# Urukul_FPGA_Supply.net
KiCad netlist of a schematic drawn in Altium Designer
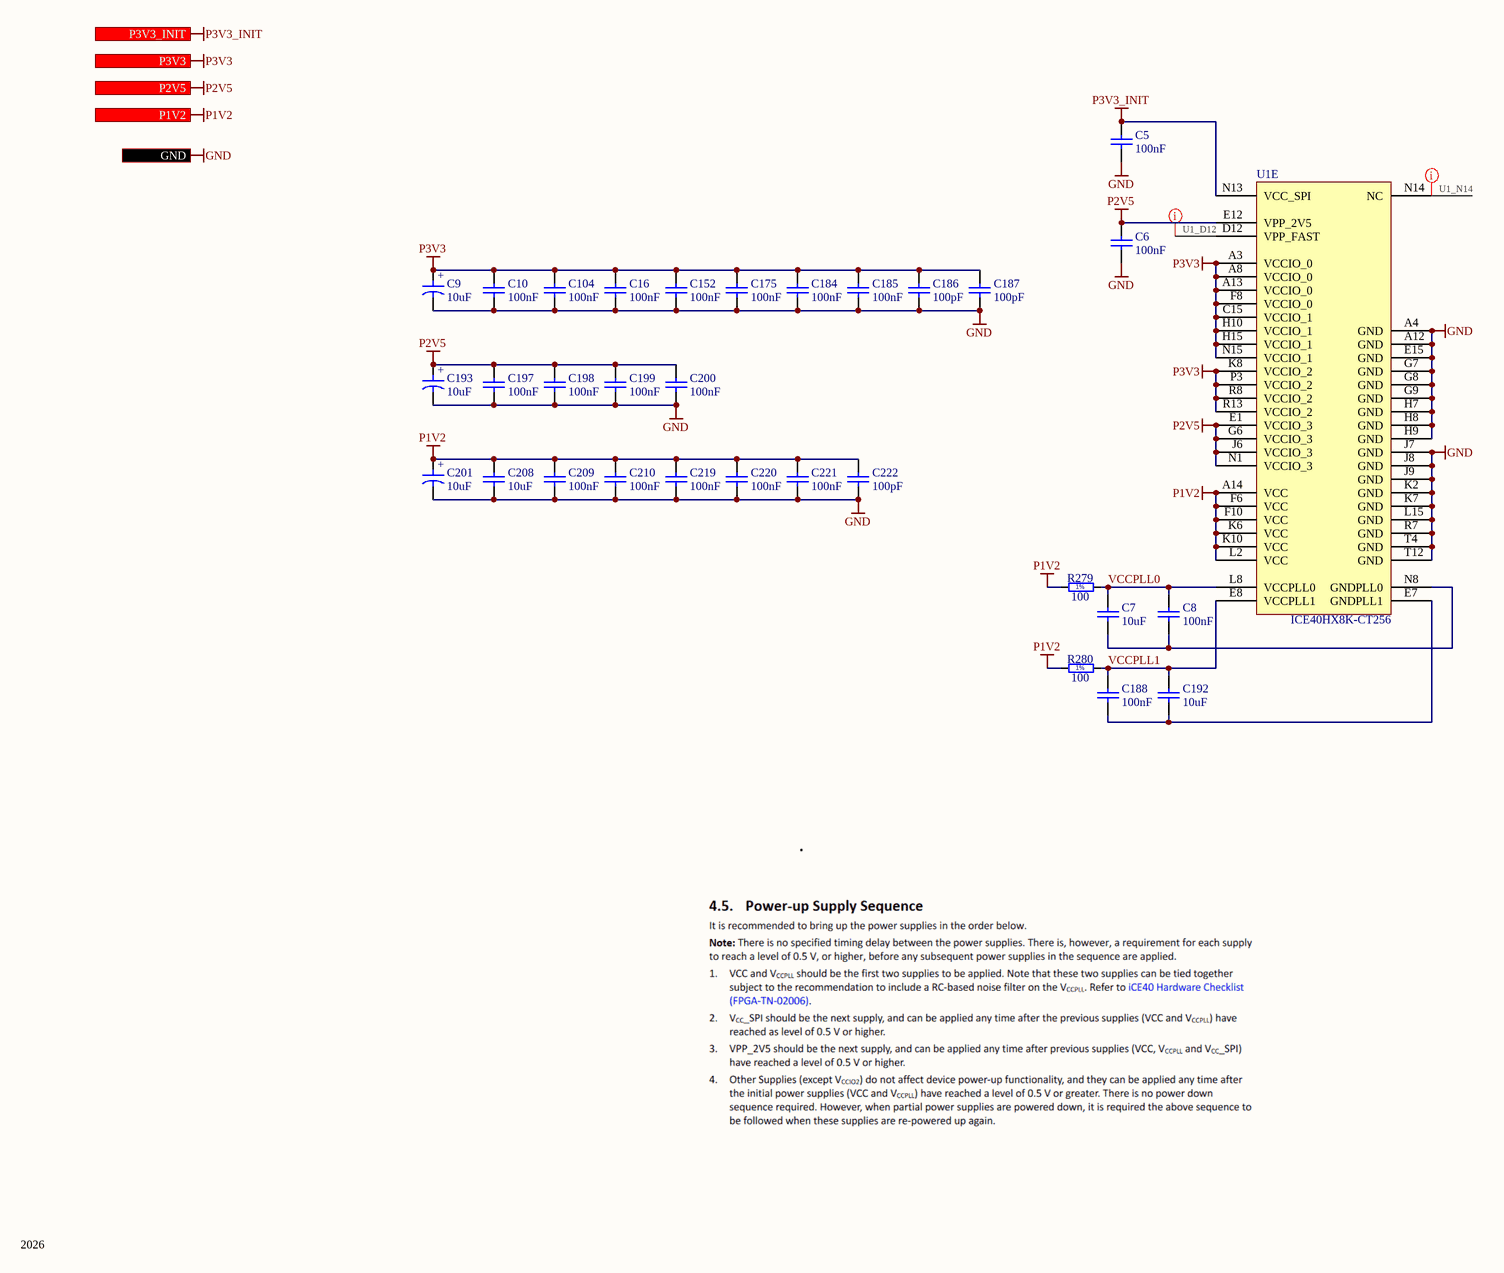
[diagram p0: Urukul_FPGA_Supply.SchDoc]

(export (version "E")
  (design (tool "Eeschema 10.0.6"))
  (components
    (comp (ref "C5")
      (value "100nF")
      (footprint "CAPC1005X55N")
      (description "Non-polarised capacitor")
      (fields
        (field (name "PART NUMBER") "CC0402_100NF_16V_10%_X5R")
        (field (name "VOLTAGE") "16V")
        (field (name "AUTHOR") "CERN DEM JLC")
      )
      (libsource (lib "Capacitors") (part "Capacitor - non polarized"))
    )
    (comp (ref "C6")
      (value "100nF")
      (footprint "CAPC1005X55N")
      (description "Non-polarised capacitor")
      (fields
        (field (name "PART NUMBER") "CC0402_100NF_16V_10%_X5R")
        (field (name "VOLTAGE") "16V")
        (field (name "AUTHOR") "CERN DEM JLC")
      )
      (libsource (lib "Capacitors") (part "Capacitor - non polarized"))
    )
    (comp (ref "C7")
      (value "10uF")
      (footprint "CAPC1005X70N")
      (description "Non-polarised capacitor")
      (fields
        (field (name "PART NUMBER") "CC0402_10UF_6.3V_20%_X5R")
        (field (name "VOLTAGE") "6.3V")
        (field (name "AUTHOR") "CERN DEM JLC")
      )
      (libsource (lib "Capacitors") (part "Capacitor - non polarized"))
    )
    (comp (ref "C8")
      (value "100nF")
      (footprint "CAPC1005X55N")
      (description "Non-polarised capacitor")
      (fields
        (field (name "PART NUMBER") "CC0402_100NF_16V_10%_X5R")
        (field (name "VOLTAGE") "16V")
        (field (name "AUTHOR") "CERN DEM JLC")
      )
      (libsource (lib "Capacitors") (part "Capacitor - non polarized"))
    )
    (comp (ref "C9")
      (value "10uF")
      (footprint "CAPMP3216X180N")
      (description "Polarised capacitor")
      (fields
        (field (name "PART NUMBER") "CTE3216-18_10UF_16V_20%_AVX_TCJ")
        (field (name "VOLTAGE") "16V")
        (field (name "AUTHOR") "CERN DEM JLC")
      )
      (libsource (lib "Capacitors") (part "Capacitor - polarized"))
    )
    (comp (ref "C10")
      (value "100nF")
      (footprint "CAPC1005X55N")
      (description "Non-polarised capacitor")
      (fields
        (field (name "PART NUMBER") "CC0402_100NF_16V_10%_X5R")
        (field (name "VOLTAGE") "16V")
        (field (name "AUTHOR") "CERN DEM JLC")
      )
      (libsource (lib "Capacitors") (part "Capacitor - non polarized"))
    )
    (comp (ref "C16")
      (value "100nF")
      (footprint "CAPC1005X55N")
      (description "Non-polarised capacitor")
      (fields
        (field (name "PART NUMBER") "CC0402_100NF_16V_10%_X5R")
        (field (name "VOLTAGE") "16V")
        (field (name "AUTHOR") "CERN DEM JLC")
      )
      (libsource (lib "Capacitors") (part "Capacitor - non polarized"))
    )
    (comp (ref "C104")
      (value "100nF")
      (footprint "CAPC1005X55N")
      (description "Non-polarised capacitor")
      (fields
        (field (name "PART NUMBER") "CC0402_100NF_16V_10%_X5R")
        (field (name "VOLTAGE") "16V")
        (field (name "AUTHOR") "CERN DEM JLC")
      )
      (libsource (lib "Capacitors") (part "Capacitor - non polarized"))
    )
    (comp (ref "C152")
      (value "100nF")
      (footprint "CAPC1005X55N")
      (description "Non-polarised capacitor")
      (fields
        (field (name "PART NUMBER") "CC0402_100NF_16V_10%_X5R")
        (field (name "VOLTAGE") "16V")
        (field (name "AUTHOR") "CERN DEM JLC")
      )
      (libsource (lib "Capacitors") (part "Capacitor - non polarized"))
    )
    (comp (ref "C175")
      (value "100nF")
      (footprint "CAPC1005X55N")
      (description "Non-polarised capacitor")
      (fields
        (field (name "PART NUMBER") "CC0402_100NF_16V_10%_X5R")
        (field (name "VOLTAGE") "16V")
        (field (name "AUTHOR") "CERN DEM JLC")
      )
      (libsource (lib "Capacitors") (part "Capacitor - non polarized"))
    )
    (comp (ref "C184")
      (value "100nF")
      (footprint "CAPC1005X55N")
      (description "Non-polarised capacitor")
      (fields
        (field (name "PART NUMBER") "CC0402_100NF_16V_10%_X5R")
        (field (name "VOLTAGE") "16V")
        (field (name "AUTHOR") "CERN DEM JLC")
      )
      (libsource (lib "Capacitors") (part "Capacitor - non polarized"))
    )
    (comp (ref "C185")
      (value "100nF")
      (footprint "CAPC1005X55N")
      (description "Non-polarised capacitor")
      (fields
        (field (name "PART NUMBER") "CC0402_100NF_16V_10%_X5R")
        (field (name "VOLTAGE") "16V")
        (field (name "AUTHOR") "CERN DEM JLC")
      )
      (libsource (lib "Capacitors") (part "Capacitor - non polarized"))
    )
    (comp (ref "C186")
      (value "100pF")
      (footprint "CAPC1005X55N")
      (description "Non-polarised capacitor")
      (fields
        (field (name "PART NUMBER") "CC0402_100PF_50V_5%_C0G")
        (field (name "VOLTAGE") "50V")
        (field (name "AUTHOR") "CERN DEM JLC")
      )
      (libsource (lib "Capacitors") (part "Capacitor - non polarized"))
    )
    (comp (ref "C187")
      (value "100pF")
      (footprint "CAPC1005X55N")
      (description "Non-polarised capacitor")
      (fields
        (field (name "PART NUMBER") "CC0402_100PF_50V_5%_C0G")
        (field (name "VOLTAGE") "50V")
        (field (name "AUTHOR") "CERN DEM JLC")
      )
      (libsource (lib "Capacitors") (part "Capacitor - non polarized"))
    )
    (comp (ref "C188")
      (value "100nF")
      (footprint "CAPC1005X55N")
      (description "Non-polarised capacitor")
      (fields
        (field (name "PART NUMBER") "CC0402_100NF_16V_10%_X5R")
        (field (name "VOLTAGE") "16V")
        (field (name "AUTHOR") "CERN DEM JLC")
      )
      (libsource (lib "Capacitors") (part "Capacitor - non polarized"))
    )
    (comp (ref "C192")
      (value "10uF")
      (footprint "CAPC1005X70N")
      (description "Non-polarised capacitor")
      (fields
        (field (name "PART NUMBER") "CC0402_10UF_6.3V_20%_X5R")
        (field (name "VOLTAGE") "6.3V")
        (field (name "AUTHOR") "CERN DEM JLC")
      )
      (libsource (lib "Capacitors") (part "Capacitor - non polarized"))
    )
    (comp (ref "C193")
      (value "10uF")
      (footprint "CAPMP3216X180N")
      (description "Polarised capacitor")
      (fields
        (field (name "PART NUMBER") "CTE3216-18_10UF_16V_20%_AVX_TCJ")
        (field (name "VOLTAGE") "16V")
        (field (name "AUTHOR") "CERN DEM JLC")
      )
      (libsource (lib "Capacitors") (part "Capacitor - polarized"))
    )
    (comp (ref "C197")
      (value "100nF")
      (footprint "CAPC1005X55N")
      (description "Non-polarised capacitor")
      (fields
        (field (name "PART NUMBER") "CC0402_100NF_16V_10%_X5R")
        (field (name "VOLTAGE") "16V")
        (field (name "AUTHOR") "CERN DEM JLC")
      )
      (libsource (lib "Capacitors") (part "Capacitor - non polarized"))
    )
    (comp (ref "C198")
      (value "100nF")
      (footprint "CAPC1005X55N")
      (description "Non-polarised capacitor")
      (fields
        (field (name "PART NUMBER") "CC0402_100NF_16V_10%_X5R")
        (field (name "VOLTAGE") "16V")
        (field (name "AUTHOR") "CERN DEM JLC")
      )
      (libsource (lib "Capacitors") (part "Capacitor - non polarized"))
    )
    (comp (ref "C199")
      (value "100nF")
      (footprint "CAPC1005X55N")
      (description "Non-polarised capacitor")
      (fields
        (field (name "PART NUMBER") "CC0402_100NF_16V_10%_X5R")
        (field (name "VOLTAGE") "16V")
        (field (name "AUTHOR") "CERN DEM JLC")
      )
      (libsource (lib "Capacitors") (part "Capacitor - non polarized"))
    )
    (comp (ref "C200")
      (value "100nF")
      (footprint "CAPC1005X55N")
      (description "Non-polarised capacitor")
      (fields
        (field (name "PART NUMBER") "CC0402_100NF_16V_10%_X5R")
        (field (name "VOLTAGE") "16V")
        (field (name "AUTHOR") "CERN DEM JLC")
      )
      (libsource (lib "Capacitors") (part "Capacitor - non polarized"))
    )
    (comp (ref "C201")
      (value "10uF")
      (footprint "CAPMP3216X180N")
      (description "Polarised capacitor")
      (fields
        (field (name "PART NUMBER") "CTE3216-18_10UF_16V_20%_AVX_TCJ")
        (field (name "VOLTAGE") "16V")
        (field (name "AUTHOR") "CERN DEM JLC")
      )
      (libsource (lib "Capacitors") (part "Capacitor - polarized"))
    )
    (comp (ref "C208")
      (value "10uF")
      (footprint "CAPC2012X135N")
      (description "Non-polarised capacitor")
      (fields
        (field (name "PART NUMBER") "CC0805_10UF_16V_10%_X5R")
        (field (name "VOLTAGE") "16V")
        (field (name "AUTHOR") "CERN DEM JLC")
      )
      (libsource (lib "Capacitors") (part "Capacitor - non polarized"))
    )
    (comp (ref "C209")
      (value "100nF")
      (footprint "CAPC1005X55N")
      (description "Non-polarised capacitor")
      (fields
        (field (name "PART NUMBER") "CC0402_100NF_16V_10%_X5R")
        (field (name "VOLTAGE") "16V")
        (field (name "AUTHOR") "CERN DEM JLC")
      )
      (libsource (lib "Capacitors") (part "Capacitor - non polarized"))
    )
    (comp (ref "C210")
      (value "100nF")
      (footprint "CAPC1005X55N")
      (description "Non-polarised capacitor")
      (fields
        (field (name "PART NUMBER") "CC0402_100NF_16V_10%_X5R")
        (field (name "VOLTAGE") "16V")
        (field (name "AUTHOR") "CERN DEM JLC")
      )
      (libsource (lib "Capacitors") (part "Capacitor - non polarized"))
    )
    (comp (ref "C219")
      (value "100nF")
      (footprint "CAPC1005X55N")
      (description "Non-polarised capacitor")
      (fields
        (field (name "PART NUMBER") "CC0402_100NF_16V_10%_X5R")
        (field (name "VOLTAGE") "16V")
        (field (name "AUTHOR") "CERN DEM JLC")
      )
      (libsource (lib "Capacitors") (part "Capacitor - non polarized"))
    )
    (comp (ref "C220")
      (value "100nF")
      (footprint "CAPC1005X55N")
      (description "Non-polarised capacitor")
      (fields
        (field (name "PART NUMBER") "CC0402_100NF_16V_10%_X5R")
        (field (name "VOLTAGE") "16V")
        (field (name "AUTHOR") "CERN DEM JLC")
      )
      (libsource (lib "Capacitors") (part "Capacitor - non polarized"))
    )
    (comp (ref "C221")
      (value "100nF")
      (footprint "CAPC1005X55N")
      (description "Non-polarised capacitor")
      (fields
        (field (name "PART NUMBER") "CC0402_100NF_16V_10%_X5R")
        (field (name "VOLTAGE") "16V")
        (field (name "AUTHOR") "CERN DEM JLC")
      )
      (libsource (lib "Capacitors") (part "Capacitor - non polarized"))
    )
    (comp (ref "C222")
      (value "100pF")
      (footprint "CAPC1005X55N")
      (description "Non-polarised capacitor")
      (fields
        (field (name "PART NUMBER") "CC0402_100PF_50V_5%_C0G")
        (field (name "VOLTAGE") "50V")
        (field (name "AUTHOR") "CERN DEM JLC")
      )
      (libsource (lib "Capacitors") (part "Capacitor - non polarized"))
    )
    (comp (ref "R279")
      (value "100")
      (footprint "RESC1005X40N")
      (description "Resistor - 1%")
      (fields
        (field (name "PART NUMBER") "R0402_100R_1%_0.0625W_100PPM")
        (field (name "POWER") "0.0625W")
        (field (name "AUTHOR") "CERN DEM JLC")
      )
      (libsource (lib "Resistors") (part "Resistor - 1%"))
    )
    (comp (ref "R280")
      (value "100")
      (footprint "RESC1005X40N")
      (description "Resistor - 1%")
      (fields
        (field (name "PART NUMBER") "R0402_100R_1%_0.0625W_100PPM")
        (field (name "POWER") "0.0625W")
        (field (name "AUTHOR") "CERN DEM JLC")
      )
      (libsource (lib "Resistors") (part "Resistor - 1%"))
    )
    (comp (ref "U1")
      (value "ICE40HX8K-CT256")
      (footprint "LATC-caBGA-256")
      (fields (field (name "MANUFACTURER") "Lattice Semiconductor"))
      (libsource (lib "Altium Content Vault") (part "LATC-HX8K-caBGA-256"))
    )
  )
  (nets
    (net (code "1") (name "/U1_D12") (class "Default")
      (node (ref "U1") (pin "D12") (pinfunction "VPP_FAST_D12") (pintype "power_in"))
    )
    (net (code "2") (name "/U1_N14") (class "Default")
      (node (ref "U1") (pin "N14") (pinfunction "NC_N14") (pintype "passive"))
    )
    (net (code "3") (name "/VCCPLL0") (class "Default")
      (node (ref "C7") (pin "2") (pinfunction "2_2") (pintype "passive"))
      (node (ref "C8") (pin "2") (pinfunction "2_2") (pintype "passive"))
      (node (ref "R279") (pin "2") (pinfunction "2_2") (pintype "passive"))
      (node (ref "U1") (pin "L8") (pinfunction "VCCPLL0_L8") (pintype "power_in"))
    )
    (net (code "4") (name "/VCCPLL1") (class "Default")
      (node (ref "C188") (pin "2") (pinfunction "2_2") (pintype "passive"))
      (node (ref "C192") (pin "2") (pinfunction "2_2") (pintype "passive"))
      (node (ref "R280") (pin "2") (pinfunction "2_2") (pintype "passive"))
      (node (ref "U1") (pin "E8") (pinfunction "VCCPLL1_E8") (pintype "power_in"))
    )
    (net (code "5") (name "GND") (class "Default")
      (node (ref "C10") (pin "1") (pinfunction "1_1") (pintype "passive"))
      (node (ref "C104") (pin "1") (pinfunction "1_1") (pintype "passive"))
      (node (ref "C152") (pin "1") (pinfunction "1_1") (pintype "passive"))
      (node (ref "C16") (pin "1") (pinfunction "1_1") (pintype "passive"))
      (node (ref "C175") (pin "1") (pinfunction "1_1") (pintype "passive"))
      (node (ref "C184") (pin "1") (pinfunction "1_1") (pintype "passive"))
      (node (ref "C185") (pin "1") (pinfunction "1_1") (pintype "passive"))
      (node (ref "C186") (pin "1") (pinfunction "1_1") (pintype "passive"))
      (node (ref "C187") (pin "1") (pinfunction "1_1") (pintype "passive"))
      (node (ref "C193") (pin "2") (pinfunction "2_2") (pintype "passive"))
      (node (ref "C197") (pin "1") (pinfunction "1_1") (pintype "passive"))
      (node (ref "C198") (pin "1") (pinfunction "1_1") (pintype "passive"))
      (node (ref "C199") (pin "1") (pinfunction "1_1") (pintype "passive"))
      (node (ref "C200") (pin "1") (pinfunction "1_1") (pintype "passive"))
      (node (ref "C201") (pin "2") (pinfunction "2_2") (pintype "passive"))
      (node (ref "C208") (pin "1") (pinfunction "1_1") (pintype "passive"))
      (node (ref "C209") (pin "1") (pinfunction "1_1") (pintype "passive"))
      (node (ref "C210") (pin "1") (pinfunction "1_1") (pintype "passive"))
      (node (ref "C219") (pin "1") (pinfunction "1_1") (pintype "passive"))
      (node (ref "C220") (pin "1") (pinfunction "1_1") (pintype "passive"))
      (node (ref "C221") (pin "1") (pinfunction "1_1") (pintype "passive"))
      (node (ref "C222") (pin "1") (pinfunction "1_1") (pintype "passive"))
      (node (ref "C5") (pin "1") (pinfunction "1_1") (pintype "passive"))
      (node (ref "C6") (pin "1") (pinfunction "1_1") (pintype "passive"))
      (node (ref "C9") (pin "2") (pinfunction "2_2") (pintype "passive"))
      (node (ref "U1") (pin "A12") (pinfunction "GND_A12") (pintype "power_in"))
      (node (ref "U1") (pin "A4") (pinfunction "GND_A4") (pintype "power_in"))
      (node (ref "U1") (pin "E15") (pinfunction "GND_E15") (pintype "power_in"))
      (node (ref "U1") (pin "G7") (pinfunction "GND_G7") (pintype "power_in"))
      (node (ref "U1") (pin "G8") (pinfunction "GND_G8") (pintype "power_in"))
      (node (ref "U1") (pin "G9") (pinfunction "GND_G9") (pintype "power_in"))
      (node (ref "U1") (pin "H7") (pinfunction "GND_H7") (pintype "power_in"))
      (node (ref "U1") (pin "H8") (pinfunction "GND_H8") (pintype "power_in"))
      (node (ref "U1") (pin "H9") (pinfunction "GND_H9") (pintype "power_in"))
      (node (ref "U1") (pin "J7") (pinfunction "GND_J7") (pintype "power_in"))
      (node (ref "U1") (pin "J8") (pinfunction "GND_J8") (pintype "power_in"))
      (node (ref "U1") (pin "J9") (pinfunction "GND_J9") (pintype "power_in"))
      (node (ref "U1") (pin "K2") (pinfunction "GND_K2") (pintype "power_in"))
      (node (ref "U1") (pin "K7") (pinfunction "GND_K7") (pintype "power_in"))
      (node (ref "U1") (pin "L15") (pinfunction "GND_L15") (pintype "power_in"))
      (node (ref "U1") (pin "R7") (pinfunction "GND_R7") (pintype "power_in"))
      (node (ref "U1") (pin "T12") (pinfunction "GND_T12") (pintype "power_in"))
      (node (ref "U1") (pin "T4") (pinfunction "GND_T4") (pintype "power_in"))
    )
    (net (code "6") (name "Net-(U1E-GNDPLL0)") (class "Default")
      (node (ref "C7") (pin "1") (pinfunction "1_1") (pintype "passive"))
      (node (ref "C8") (pin "1") (pinfunction "1_1") (pintype "passive"))
      (node (ref "U1") (pin "N8") (pinfunction "GNDPLL0_N8") (pintype "power_in"))
    )
    (net (code "7") (name "Net-(U1E-GNDPLL1)") (class "Default")
      (node (ref "C188") (pin "1") (pinfunction "1_1") (pintype "passive"))
      (node (ref "C192") (pin "1") (pinfunction "1_1") (pintype "passive"))
      (node (ref "U1") (pin "E7") (pinfunction "GNDPLL1_E7") (pintype "power_in"))
    )
    (net (code "8") (name "P1V2") (class "Default")
      (node (ref "C201") (pin "1") (pinfunction "1_1") (pintype "passive"))
      (node (ref "C208") (pin "2") (pinfunction "2_2") (pintype "passive"))
      (node (ref "C209") (pin "2") (pinfunction "2_2") (pintype "passive"))
      (node (ref "C210") (pin "2") (pinfunction "2_2") (pintype "passive"))
      (node (ref "C219") (pin "2") (pinfunction "2_2") (pintype "passive"))
      (node (ref "C220") (pin "2") (pinfunction "2_2") (pintype "passive"))
      (node (ref "C221") (pin "2") (pinfunction "2_2") (pintype "passive"))
      (node (ref "C222") (pin "2") (pinfunction "2_2") (pintype "passive"))
      (node (ref "R279") (pin "1") (pinfunction "1_1") (pintype "passive"))
      (node (ref "R280") (pin "1") (pinfunction "1_1") (pintype "passive"))
      (node (ref "U1") (pin "A14") (pinfunction "VCC_A14") (pintype "power_in"))
      (node (ref "U1") (pin "F10") (pinfunction "VCC_F10") (pintype "power_in"))
      (node (ref "U1") (pin "F6") (pinfunction "VCC_F6") (pintype "power_in"))
      (node (ref "U1") (pin "K10") (pinfunction "VCC_K10") (pintype "power_in"))
      (node (ref "U1") (pin "K6") (pinfunction "VCC_K6") (pintype "power_in"))
      (node (ref "U1") (pin "L2") (pinfunction "VCC_L2") (pintype "power_in"))
    )
    (net (code "9") (name "P2V5") (class "Default")
      (node (ref "C193") (pin "1") (pinfunction "1_1") (pintype "passive"))
      (node (ref "C197") (pin "2") (pinfunction "2_2") (pintype "passive"))
      (node (ref "C198") (pin "2") (pinfunction "2_2") (pintype "passive"))
      (node (ref "C199") (pin "2") (pinfunction "2_2") (pintype "passive"))
      (node (ref "C200") (pin "2") (pinfunction "2_2") (pintype "passive"))
      (node (ref "C6") (pin "2") (pinfunction "2_2") (pintype "passive"))
      (node (ref "U1") (pin "E1") (pinfunction "VCCIO_3_E1") (pintype "power_in"))
      (node (ref "U1") (pin "E12") (pinfunction "VPP_2V5_E12") (pintype "power_in"))
      (node (ref "U1") (pin "G6") (pinfunction "VCCIO_3_G6") (pintype "power_in"))
      (node (ref "U1") (pin "J6") (pinfunction "VCCIO_3_J6") (pintype "power_in"))
      (node (ref "U1") (pin "N1") (pinfunction "VCCIO_3_N1") (pintype "power_in"))
    )
    (net (code "10") (name "P3V3") (class "Default")
      (node (ref "C10") (pin "2") (pinfunction "2_2") (pintype "passive"))
      (node (ref "C104") (pin "2") (pinfunction "2_2") (pintype "passive"))
      (node (ref "C152") (pin "2") (pinfunction "2_2") (pintype "passive"))
      (node (ref "C16") (pin "2") (pinfunction "2_2") (pintype "passive"))
      (node (ref "C175") (pin "2") (pinfunction "2_2") (pintype "passive"))
      (node (ref "C184") (pin "2") (pinfunction "2_2") (pintype "passive"))
      (node (ref "C185") (pin "2") (pinfunction "2_2") (pintype "passive"))
      (node (ref "C186") (pin "2") (pinfunction "2_2") (pintype "passive"))
      (node (ref "C187") (pin "2") (pinfunction "2_2") (pintype "passive"))
      (node (ref "C9") (pin "1") (pinfunction "1_1") (pintype "passive"))
      (node (ref "U1") (pin "A13") (pinfunction "VCCIO_0_A13") (pintype "power_in"))
      (node (ref "U1") (pin "A3") (pinfunction "VCCIO_0_A3") (pintype "power_in"))
      (node (ref "U1") (pin "A8") (pinfunction "VCCIO_0_A8") (pintype "power_in"))
      (node (ref "U1") (pin "C15") (pinfunction "VCCIO_1_C15") (pintype "power_in"))
      (node (ref "U1") (pin "F8") (pinfunction "VCCIO_0_F8") (pintype "power_in"))
      (node (ref "U1") (pin "H10") (pinfunction "VCCIO_1_H10") (pintype "power_in"))
      (node (ref "U1") (pin "H15") (pinfunction "VCCIO_1_H15") (pintype "power_in"))
      (node (ref "U1") (pin "K8") (pinfunction "VCCIO_2_K8") (pintype "power_in"))
      (node (ref "U1") (pin "N15") (pinfunction "VCCIO_1_N15") (pintype "power_in"))
      (node (ref "U1") (pin "P3") (pinfunction "VCCIO_2_P3") (pintype "power_in"))
      (node (ref "U1") (pin "R13") (pinfunction "VCCIO_2_R13") (pintype "power_in"))
      (node (ref "U1") (pin "R8") (pinfunction "VCCIO_2_R8") (pintype "power_in"))
    )
    (net (code "11") (name "P3V3_INIT") (class "Default")
      (node (ref "C5") (pin "2") (pinfunction "2_2") (pintype "passive"))
      (node (ref "U1") (pin "N13") (pinfunction "VCC_SPI_N13") (pintype "power_in"))
    )
  )
)
